# FPGA_CFG.net
KiCad netlist of a schematic drawn in Altium Designer
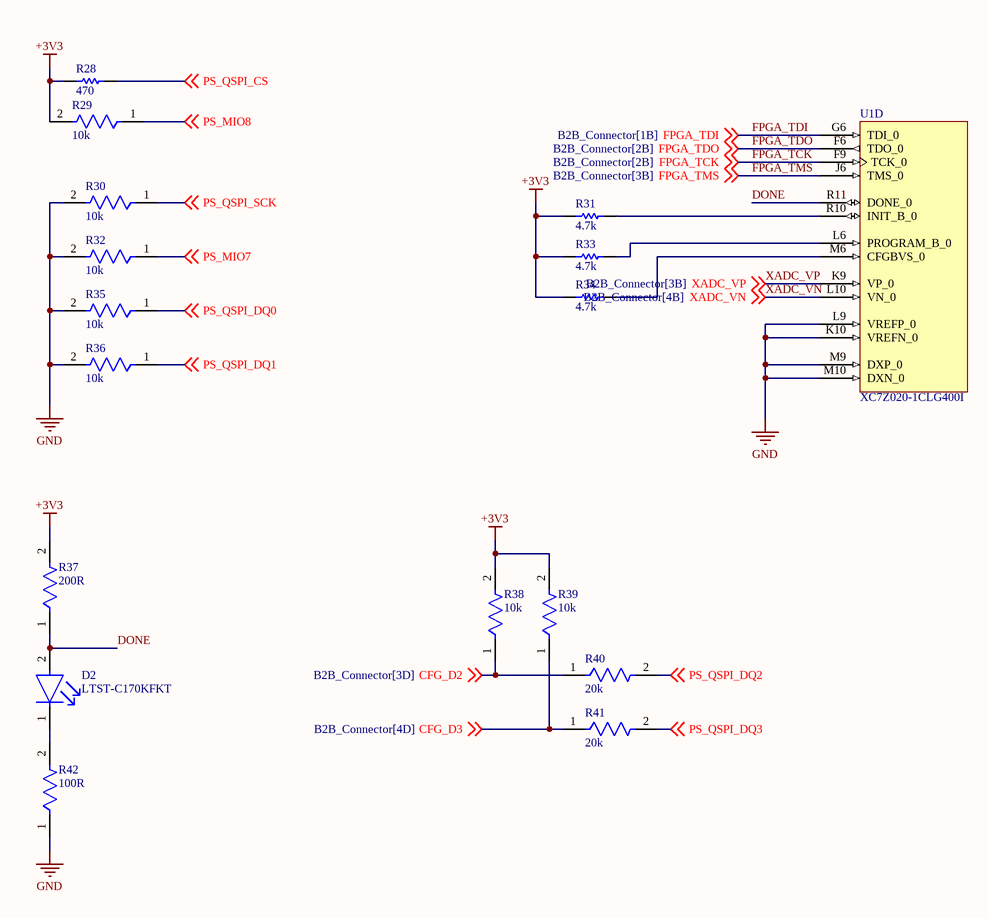
[diagram p0: FPGA_CFG.SchDoc]

(export (version "E")
  (design (tool "Eeschema 10.0.6"))
  (components
    (comp (ref "D2")
      (value "LTST-C170KFKT")
      (footprint "FP-LTST-C170KFKT-MFG")
      (description "LED ORANGE CLEAR SMD")
      (libsource (lib "Altium Content Vault") (part "8706943c75ba83719d021d2fdc84c58"))
    )
    (comp (ref "R28")
      (value "470")
      (footprint "RESC1608X55X25LL10T15")
      (libsource (lib "Altium Content Vault") (part "RES-2"))
    )
    (comp (ref "R29")
      (value "10k")
      (footprint "FP-RC0603-0_55-IPC_C")
      (description "RES 10K OHM 1% 1/10W 0603")
      (fields (field (name "TOLERANCE") "1%"))
      (libsource (lib "Altium Content Vault") (part "1029c3af85768c4190bb7ad29bc67b5"))
    )
    (comp (ref "R30")
      (value "10k")
      (footprint "FP-RC0603-0_55-IPC_C")
      (description "RES 10K OHM 1% 1/10W 0603")
      (fields (field (name "TOLERANCE") "1%"))
      (libsource (lib "Altium Content Vault") (part "1029c3af85768c4190bb7ad29bc67b5"))
    )
    (comp (ref "R31")
      (value "4.7k")
      (footprint "RESC1608X55X25LL10T15")
      (description "Chip Resistor, 4.7 KOhm, +/- 1%, 0.1 W, -55 to 155 degC, 0603 (1608 Metric), RoHS, Tape and Reel")
      (fields (field (name "MANUFACTURER") "Yageo") (field (name "TOLERANCE") "1%"))
      (libsource (lib "Altium Content Vault") (part "RES-2"))
    )
    (comp (ref "R32")
      (value "10k")
      (footprint "FP-RC0603-0_55-IPC_C")
      (description "RES 10K OHM 1% 1/10W 0603")
      (fields (field (name "TOLERANCE") "1%"))
      (libsource (lib "Altium Content Vault") (part "1029c3af85768c4190bb7ad29bc67b5"))
    )
    (comp (ref "R33")
      (value "4.7k")
      (footprint "RESC1608X55X25LL10T15")
      (description "Chip Resistor, 4.7 KOhm, +/- 1%, 0.1 W, -55 to 155 degC, 0603 (1608 Metric), RoHS, Tape and Reel")
      (fields (field (name "MANUFACTURER") "Yageo") (field (name "TOLERANCE") "1%"))
      (libsource (lib "Altium Content Vault") (part "RES-2"))
    )
    (comp (ref "R34")
      (value "4.7k")
      (footprint "RESC1608X55X25LL10T15")
      (description "Chip Resistor, 4.7 KOhm, +/- 1%, 0.1 W, -55 to 155 degC, 0603 (1608 Metric), RoHS, Tape and Reel")
      (fields (field (name "MANUFACTURER") "Yageo") (field (name "TOLERANCE") "1%"))
      (libsource (lib "Altium Content Vault") (part "RES-2"))
    )
    (comp (ref "R35")
      (value "10k")
      (footprint "FP-RC0603-0_55-IPC_C")
      (description "RES 10K OHM 1% 1/10W 0603")
      (fields (field (name "TOLERANCE") "1%"))
      (libsource (lib "Altium Content Vault") (part "1029c3af85768c4190bb7ad29bc67b5"))
    )
    (comp (ref "R36")
      (value "10k")
      (footprint "FP-RC0603-0_55-IPC_C")
      (description "RES 10K OHM 1% 1/10W 0603")
      (fields (field (name "TOLERANCE") "1%"))
      (libsource (lib "Altium Content Vault") (part "1029c3af85768c4190bb7ad29bc67b5"))
    )
    (comp (ref "R37")
      (value "200R")
      (footprint "FP-ERA3A-IPC_C")
      (description "RES SMD 200 OHM 0.1% 1/10W 0603")
      (fields (field (name "TOLERANCE") "0.1%"))
      (libsource (lib "Altium Content Vault") (part "1029c3af85768c4190bb7ad29bc67b5"))
    )
    (comp (ref "R38")
      (value "10k")
      (footprint "FP-RC0603-0_55-IPC_C")
      (description "RES 10K OHM 1% 1/10W 0603")
      (fields (field (name "TOLERANCE") "1%"))
      (libsource (lib "Altium Content Vault") (part "1029c3af85768c4190bb7ad29bc67b5"))
    )
    (comp (ref "R39")
      (value "10k")
      (footprint "FP-RC0603-0_55-IPC_C")
      (description "RES 10K OHM 1% 1/10W 0603")
      (fields (field (name "TOLERANCE") "1%"))
      (libsource (lib "Altium Content Vault") (part "1029c3af85768c4190bb7ad29bc67b5"))
    )
    (comp (ref "R40")
      (value "20k")
      (footprint "FP-RT0603-MFG")
      (description "RES SMD 20K OHM 0.1% 1/10W 0603")
      (fields
        (field (name "MANUFACTURER") "Yageo")
        (field (name "OCTOPART") "https://octopart.com/rt0603brd0720kl-yageo-1382430")
      )
      (libsource (lib "Altium Content Vault") (part "1029c3af85768c4190bb7ad29bc67b5"))
    )
    (comp (ref "R41")
      (value "20k")
      (footprint "FP-RT0603-MFG")
      (description "RES SMD 20K OHM 0.1% 1/10W 0603")
      (fields
        (field (name "MANUFACTURER") "Yageo")
        (field (name "OCTOPART") "https://octopart.com/rt0603brd0720kl-yageo-1382430")
      )
      (libsource (lib "Altium Content Vault") (part "1029c3af85768c4190bb7ad29bc67b5"))
    )
    (comp (ref "R42")
      (value "100R")
      (footprint "FP-RC0603-0_55-MFG")
      (fields (field (name "TOLERANCE") "1%"))
      (libsource (lib "Altium Content Vault") (part "1029c3af85768c4190bb7ad29bc67b5"))
    )
    (comp (ref "U1")
      (value "XC7Z020-1CLG400I")
      (footprint "CLG400")
      (fields (field (name "GENERIC PART NUMBER") "XC7Z020"))
      (libsource (lib "Altium Content Vault") (part "XNLX-XC7Z020-CLG400"))
    )
  )
  (nets
    (net (code "1") (name "+3V3") (class "Default")
      (node (ref "R28") (pin "2") (pinfunction "2_2") (pintype "passive"))
      (node (ref "R29") (pin "2") (pinfunction "2_2") (pintype "passive"))
      (node (ref "R31") (pin "2") (pinfunction "2_2") (pintype "passive"))
      (node (ref "R33") (pin "2") (pinfunction "2_2") (pintype "passive"))
      (node (ref "R34") (pin "2") (pinfunction "2_2") (pintype "passive"))
      (node (ref "R37") (pin "2") (pinfunction "2_2") (pintype "passive"))
      (node (ref "R38") (pin "2") (pinfunction "2_2") (pintype "passive"))
      (node (ref "R39") (pin "2") (pinfunction "2_2") (pintype "passive"))
    )
    (net (code "2") (name "/DONE") (class "Default")
      (node (ref "D2") (pin "2") (pinfunction "A_2") (pintype "passive"))
      (node (ref "R37") (pin "1") (pinfunction "1_1") (pintype "passive"))
      (node (ref "U1") (pin "R11") (pinfunction "DONE_0_R11") (pintype "bidirectional"))
    )
    (net (code "3") (name "CFG_D2") (class "Default")
      (node (ref "R38") (pin "1") (pinfunction "1_1") (pintype "passive"))
      (node (ref "R40") (pin "1") (pinfunction "1_1") (pintype "passive"))
    )
    (net (code "4") (name "CFG_D3") (class "Default")
      (node (ref "R39") (pin "1") (pinfunction "1_1") (pintype "passive"))
      (node (ref "R41") (pin "1") (pinfunction "1_1") (pintype "passive"))
    )
    (net (code "5") (name "FPGA_TCK") (class "Default")
      (node (ref "U1") (pin "F9") (pinfunction "TCK_0_F9") (pintype "input"))
    )
    (net (code "6") (name "FPGA_TDI") (class "Default")
      (node (ref "U1") (pin "G6") (pinfunction "TDI_0_G6") (pintype "input"))
    )
    (net (code "7") (name "FPGA_TDO") (class "Default")
      (node (ref "U1") (pin "F6") (pinfunction "TDO_0_F6") (pintype "output"))
    )
    (net (code "8") (name "FPGA_TMS") (class "Default")
      (node (ref "U1") (pin "J6") (pinfunction "TMS_0_J6") (pintype "input"))
    )
    (net (code "9") (name "GND") (class "Default")
      (node (ref "R30") (pin "2") (pinfunction "2_2") (pintype "passive"))
      (node (ref "R32") (pin "2") (pinfunction "2_2") (pintype "passive"))
      (node (ref "R35") (pin "2") (pinfunction "2_2") (pintype "passive"))
      (node (ref "R36") (pin "2") (pinfunction "2_2") (pintype "passive"))
      (node (ref "R42") (pin "1") (pinfunction "1_1") (pintype "passive"))
      (node (ref "U1") (pin "K10") (pinfunction "VREFN_0_K10") (pintype "input"))
      (node (ref "U1") (pin "L9") (pinfunction "VREFP_0_L9") (pintype "input"))
      (node (ref "U1") (pin "M10") (pinfunction "DXN_0_M10") (pintype "input"))
      (node (ref "U1") (pin "M9") (pinfunction "DXP_0_M9") (pintype "input"))
    )
    (net (code "10") (name "Net-(D2-C)") (class "Default")
      (node (ref "D2") (pin "1") (pinfunction "C_1") (pintype "passive"))
      (node (ref "R42") (pin "2") (pinfunction "2_2") (pintype "passive"))
    )
    (net (code "11") (name "Net-(U1D-CFGBVS_0)") (class "Default")
      (node (ref "R34") (pin "1") (pinfunction "1_1") (pintype "passive"))
      (node (ref "U1") (pin "M6") (pinfunction "CFGBVS_0_M6") (pintype "input"))
    )
    (net (code "12") (name "Net-(U1D-INIT_B_0)") (class "Default")
      (node (ref "R31") (pin "1") (pinfunction "1_1") (pintype "passive"))
      (node (ref "U1") (pin "R10") (pinfunction "INIT_B_0_R10") (pintype "bidirectional"))
    )
    (net (code "13") (name "Net-(U1D-PROGRAM_B_0)") (class "Default")
      (node (ref "R33") (pin "1") (pinfunction "1_1") (pintype "passive"))
      (node (ref "U1") (pin "L6") (pinfunction "PROGRAM_B_0_L6") (pintype "input"))
    )
    (net (code "14") (name "PS_MIO7") (class "Default")
      (node (ref "R32") (pin "1") (pinfunction "1_1") (pintype "passive"))
    )
    (net (code "15") (name "PS_MIO8") (class "Default")
      (node (ref "R29") (pin "1") (pinfunction "1_1") (pintype "passive"))
    )
    (net (code "16") (name "PS_QSPI_CS") (class "Default")
      (node (ref "R28") (pin "1") (pinfunction "1_1") (pintype "passive"))
    )
    (net (code "17") (name "PS_QSPI_DQ0") (class "Default")
      (node (ref "R35") (pin "1") (pinfunction "1_1") (pintype "passive"))
    )
    (net (code "18") (name "PS_QSPI_DQ1") (class "Default")
      (node (ref "R36") (pin "1") (pinfunction "1_1") (pintype "passive"))
    )
    (net (code "19") (name "PS_QSPI_DQ2") (class "Default")
      (node (ref "R40") (pin "2") (pinfunction "2_2") (pintype "passive"))
    )
    (net (code "20") (name "PS_QSPI_DQ3") (class "Default")
      (node (ref "R41") (pin "2") (pinfunction "2_2") (pintype "passive"))
    )
    (net (code "21") (name "PS_QSPI_SCK") (class "Default")
      (node (ref "R30") (pin "1") (pinfunction "1_1") (pintype "passive"))
    )
    (net (code "22") (name "XADC_VN") (class "Default")
      (node (ref "U1") (pin "L10") (pinfunction "VN_0_L10") (pintype "input"))
    )
    (net (code "23") (name "XADC_VP") (class "Default")
      (node (ref "U1") (pin "K9") (pinfunction "VP_0_K9") (pintype "input"))
    )
  )
)
